# matrix_mixer_rev02_7eurorack.net
KiCad netlist of a schematic drawn in EAGLE
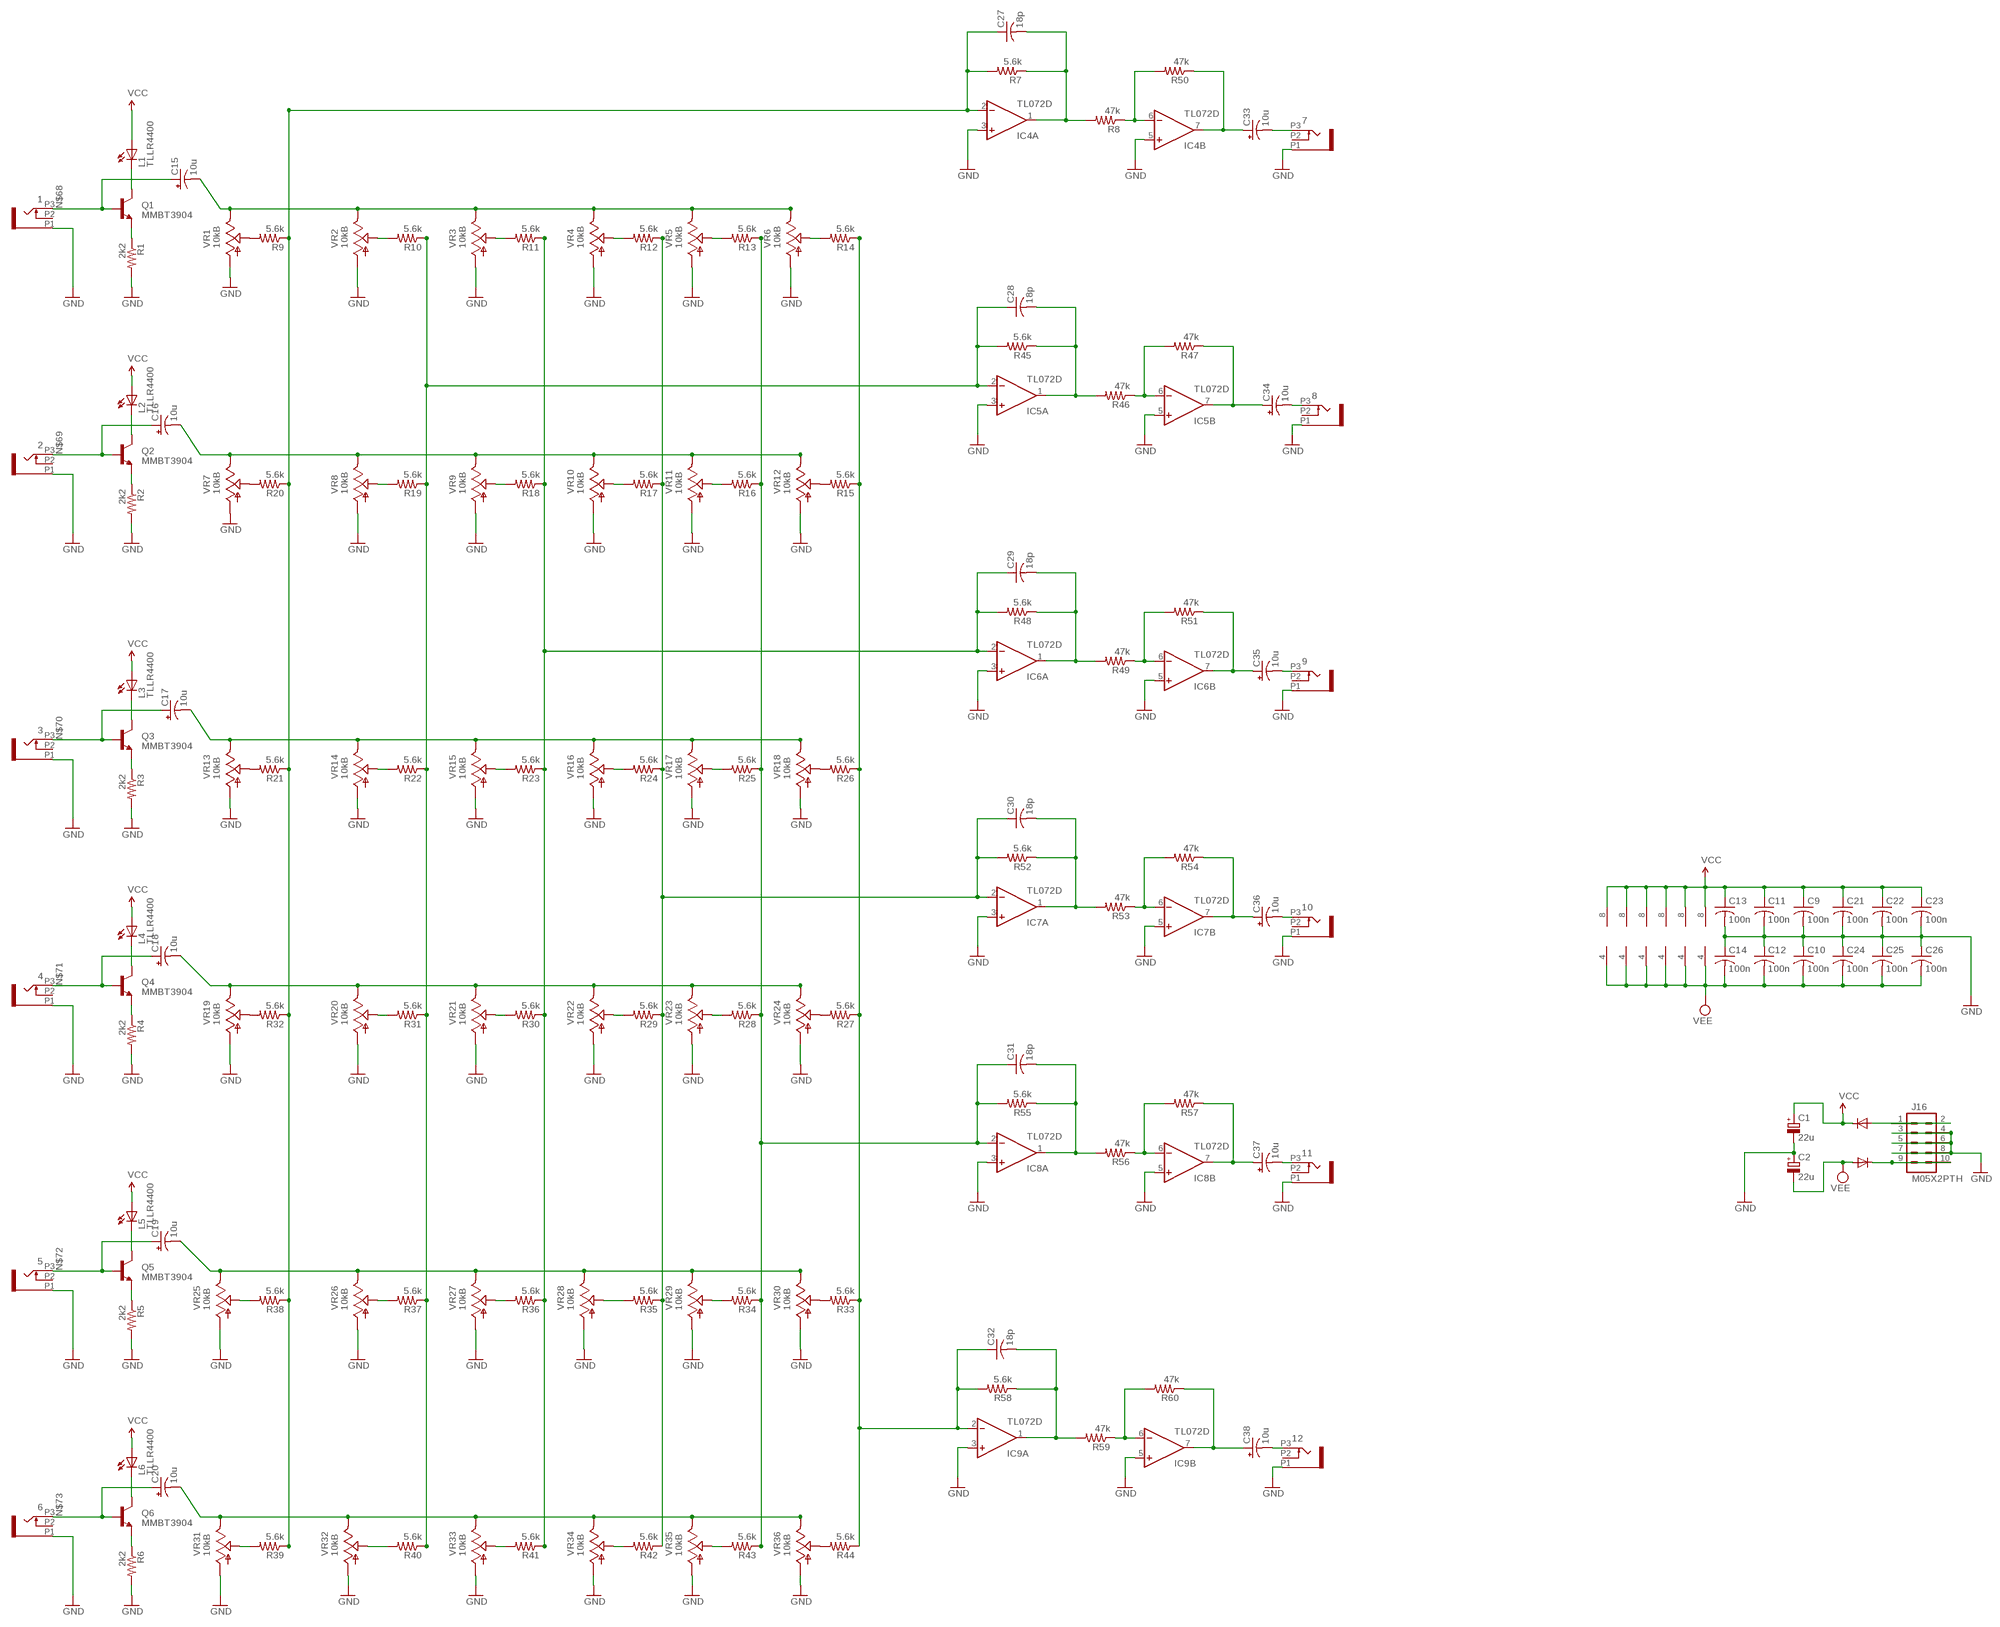
[diagram p0: schematic, sheet 1]

(export (version "E")
  (design (tool "Eeschema 10.0.6"))
  (components
    (comp (ref "1")
      (value "PJ301_THONKICONN6")
      (footprint "eagle-import:WQP_PJ_301M6")
      (libsource (lib "eagle-import") (part "PJ301_THONKICONN6"))
    )
    (comp (ref "2")
      (value "PJ301_THONKICONN6")
      (footprint "eagle-import:WQP_PJ_301M6")
      (libsource (lib "eagle-import") (part "PJ301_THONKICONN6"))
    )
    (comp (ref "3")
      (value "PJ301_THONKICONN6")
      (footprint "eagle-import:WQP_PJ_301M6")
      (libsource (lib "eagle-import") (part "PJ301_THONKICONN6"))
    )
    (comp (ref "4")
      (value "PJ301_THONKICONN6")
      (footprint "eagle-import:WQP_PJ_301M6")
      (libsource (lib "eagle-import") (part "PJ301_THONKICONN6"))
    )
    (comp (ref "5")
      (value "PJ301_THONKICONN6")
      (footprint "eagle-import:WQP_PJ_301M6")
      (libsource (lib "eagle-import") (part "PJ301_THONKICONN6"))
    )
    (comp (ref "6")
      (value "PJ301_THONKICONN6")
      (footprint "eagle-import:WQP_PJ_301M6")
      (libsource (lib "eagle-import") (part "PJ301_THONKICONN6"))
    )
    (comp (ref "7")
      (value "PJ301_THONKICONN6")
      (footprint "eagle-import:WQP_PJ_301M6")
      (libsource (lib "eagle-import") (part "PJ301_THONKICONN6"))
    )
    (comp (ref "8")
      (value "PJ301_THONKICONN6")
      (footprint "eagle-import:WQP_PJ_301M6")
      (libsource (lib "eagle-import") (part "PJ301_THONKICONN6"))
    )
    (comp (ref "9")
      (value "PJ301_THONKICONN6")
      (footprint "eagle-import:WQP_PJ_301M6")
      (libsource (lib "eagle-import") (part "PJ301_THONKICONN6"))
    )
    (comp (ref "10")
      (value "PJ301_THONKICONN6")
      (footprint "eagle-import:WQP_PJ_301M6")
      (libsource (lib "eagle-import") (part "PJ301_THONKICONN6"))
    )
    (comp (ref "11")
      (value "PJ301_THONKICONN6")
      (footprint "eagle-import:WQP_PJ_301M6")
      (libsource (lib "eagle-import") (part "PJ301_THONKICONN6"))
    )
    (comp (ref "12")
      (value "PJ301_THONKICONN6")
      (footprint "eagle-import:WQP_PJ_301M6")
      (libsource (lib "eagle-import") (part "PJ301_THONKICONN6"))
    )
    (comp (ref "C1")
      (value "22u")
      (footprint "eagle-import:PANASONIC_D")
      (libsource (lib "eagle-import") (part "CPOL-EUD"))
    )
    (comp (ref "C2")
      (value "22u")
      (footprint "eagle-import:PANASONIC_D")
      (libsource (lib "eagle-import") (part "CPOL-EUD"))
    )
    (comp (ref "C9")
      (value "100n")
      (footprint "eagle-import:C0603")
      (libsource (lib "eagle-import") (part "C-USC0603"))
    )
    (comp (ref "C10")
      (value "100n")
      (footprint "eagle-import:C0603")
      (libsource (lib "eagle-import") (part "C-USC0603"))
    )
    (comp (ref "C11")
      (value "100n")
      (footprint "eagle-import:C0603")
      (libsource (lib "eagle-import") (part "C-USC0603"))
    )
    (comp (ref "C12")
      (value "100n")
      (footprint "eagle-import:C0603")
      (libsource (lib "eagle-import") (part "C-USC0603"))
    )
    (comp (ref "C13")
      (value "100n")
      (footprint "eagle-import:C0603")
      (libsource (lib "eagle-import") (part "C-USC0603"))
    )
    (comp (ref "C14")
      (value "100n")
      (footprint "eagle-import:C0603")
      (libsource (lib "eagle-import") (part "C-USC0603"))
    )
    (comp (ref "C15")
      (value "10u")
      (footprint "eagle-import:PANASONIC_B")
      (libsource (lib "eagle-import") (part "CPOL-USB"))
    )
    (comp (ref "C16")
      (value "10u")
      (footprint "eagle-import:PANASONIC_B")
      (libsource (lib "eagle-import") (part "CPOL-USB"))
    )
    (comp (ref "C17")
      (value "10u")
      (footprint "eagle-import:PANASONIC_B")
      (libsource (lib "eagle-import") (part "CPOL-USB"))
    )
    (comp (ref "C18")
      (value "10u")
      (footprint "eagle-import:PANASONIC_B")
      (libsource (lib "eagle-import") (part "CPOL-USB"))
    )
    (comp (ref "C19")
      (value "10u")
      (footprint "eagle-import:PANASONIC_B")
      (libsource (lib "eagle-import") (part "CPOL-USB"))
    )
    (comp (ref "C20")
      (value "10u")
      (footprint "eagle-import:PANASONIC_B")
      (libsource (lib "eagle-import") (part "CPOL-USB"))
    )
    (comp (ref "C21")
      (value "100n")
      (footprint "eagle-import:C0603")
      (libsource (lib "eagle-import") (part "C-USC0603"))
    )
    (comp (ref "C22")
      (value "100n")
      (footprint "eagle-import:C0603")
      (libsource (lib "eagle-import") (part "C-USC0603"))
    )
    (comp (ref "C23")
      (value "100n")
      (footprint "eagle-import:C0603")
      (libsource (lib "eagle-import") (part "C-USC0603"))
    )
    (comp (ref "C24")
      (value "100n")
      (footprint "eagle-import:C0603")
      (libsource (lib "eagle-import") (part "C-USC0603"))
    )
    (comp (ref "C25")
      (value "100n")
      (footprint "eagle-import:C0603")
      (libsource (lib "eagle-import") (part "C-USC0603"))
    )
    (comp (ref "C26")
      (value "100n")
      (footprint "eagle-import:C0603")
      (libsource (lib "eagle-import") (part "C-USC0603"))
    )
    (comp (ref "C27")
      (value "18p")
      (footprint "eagle-import:C0603")
      (libsource (lib "eagle-import") (part "C-USC0603"))
    )
    (comp (ref "C28")
      (value "18p")
      (footprint "eagle-import:C0603")
      (libsource (lib "eagle-import") (part "C-USC0603"))
    )
    (comp (ref "C29")
      (value "18p")
      (footprint "eagle-import:C0603")
      (libsource (lib "eagle-import") (part "C-USC0603"))
    )
    (comp (ref "C30")
      (value "18p")
      (footprint "eagle-import:C0603")
      (libsource (lib "eagle-import") (part "C-USC0603"))
    )
    (comp (ref "C31")
      (value "18p")
      (footprint "eagle-import:C0603")
      (libsource (lib "eagle-import") (part "C-USC0603"))
    )
    (comp (ref "C32")
      (value "18p")
      (footprint "eagle-import:C0603")
      (libsource (lib "eagle-import") (part "C-USC0603"))
    )
    (comp (ref "C33")
      (value "10u")
      (footprint "eagle-import:PANASONIC_B")
      (libsource (lib "eagle-import") (part "CPOL-USB"))
    )
    (comp (ref "C34")
      (value "10u")
      (footprint "eagle-import:PANASONIC_B")
      (libsource (lib "eagle-import") (part "CPOL-USB"))
    )
    (comp (ref "C35")
      (value "10u")
      (footprint "eagle-import:PANASONIC_B")
      (libsource (lib "eagle-import") (part "CPOL-USB"))
    )
    (comp (ref "C36")
      (value "10u")
      (footprint "eagle-import:PANASONIC_B")
      (libsource (lib "eagle-import") (part "CPOL-USB"))
    )
    (comp (ref "C37")
      (value "10u")
      (footprint "eagle-import:PANASONIC_B")
      (libsource (lib "eagle-import") (part "CPOL-USB"))
    )
    (comp (ref "C38")
      (value "10u")
      (footprint "eagle-import:PANASONIC_B")
      (libsource (lib "eagle-import") (part "CPOL-USB"))
    )
    (comp (ref "D1")
      (value "1N5819HW")
      (footprint "eagle-import:SOD123")
      (libsource (lib "eagle-import") (part "DIODE-SOD123"))
    )
    (comp (ref "D2")
      (value "1N5819HW")
      (footprint "eagle-import:SOD123")
      (libsource (lib "eagle-import") (part "DIODE-SOD123"))
    )
    (comp (ref "IC4")
      (value "TL072D")
      (footprint "eagle-import:SO08")
      (libsource (lib "eagle-import") (part "TL072D"))
    )
    (comp (ref "IC5")
      (value "TL072D")
      (footprint "eagle-import:SO08")
      (libsource (lib "eagle-import") (part "TL072D"))
    )
    (comp (ref "IC6")
      (value "TL072D")
      (footprint "eagle-import:SO08")
      (libsource (lib "eagle-import") (part "TL072D"))
    )
    (comp (ref "IC7")
      (value "TL072D")
      (footprint "eagle-import:SO08")
      (libsource (lib "eagle-import") (part "TL072D"))
    )
    (comp (ref "IC8")
      (value "TL072D")
      (footprint "eagle-import:SO08")
      (libsource (lib "eagle-import") (part "TL072D"))
    )
    (comp (ref "IC9")
      (value "TL072D")
      (footprint "eagle-import:SO08")
      (libsource (lib "eagle-import") (part "TL072D"))
    )
    (comp (ref "J16")
      (value "M05X2PTH")
      (footprint "eagle-import:AVR_ICSP")
      (libsource (lib "eagle-import") (part "M05X2PTH"))
    )
    (comp (ref "L1")
      (value "TLLR4400")
      (footprint "eagle-import:LED3MM")
      (fields (field (name "MF") "VISHAY SEMICONDUCTOR"))
      (libsource (lib "eagle-import") (part "TLLR4400"))
    )
    (comp (ref "L2")
      (value "TLLR4400")
      (footprint "eagle-import:LED3MM")
      (fields (field (name "MF") "VISHAY SEMICONDUCTOR"))
      (libsource (lib "eagle-import") (part "TLLR4400"))
    )
    (comp (ref "L3")
      (value "TLLR4400")
      (footprint "eagle-import:LED3MM")
      (fields (field (name "MF") "VISHAY SEMICONDUCTOR"))
      (libsource (lib "eagle-import") (part "TLLR4400"))
    )
    (comp (ref "L4")
      (value "TLLR4400")
      (footprint "eagle-import:LED3MM")
      (fields (field (name "MF") "VISHAY SEMICONDUCTOR"))
      (libsource (lib "eagle-import") (part "TLLR4400"))
    )
    (comp (ref "L5")
      (value "TLLR4400")
      (footprint "eagle-import:LED3MM")
      (fields (field (name "MF") "VISHAY SEMICONDUCTOR"))
      (libsource (lib "eagle-import") (part "TLLR4400"))
    )
    (comp (ref "L6")
      (value "TLLR4400")
      (footprint "eagle-import:LED3MM")
      (fields (field (name "MF") "VISHAY SEMICONDUCTOR"))
      (libsource (lib "eagle-import") (part "TLLR4400"))
    )
    (comp (ref "Q1")
      (value "MMBT3904")
      (footprint "eagle-import:SOT23-BEC")
      (libsource (lib "eagle-import") (part "-NPN-SOT23-BECMMBT3904LT1"))
    )
    (comp (ref "Q2")
      (value "MMBT3904")
      (footprint "eagle-import:SOT23-BEC")
      (libsource (lib "eagle-import") (part "-NPN-SOT23-BECMMBT3904LT1"))
    )
    (comp (ref "Q3")
      (value "MMBT3904")
      (footprint "eagle-import:SOT23-BEC")
      (libsource (lib "eagle-import") (part "-NPN-SOT23-BECMMBT3904LT1"))
    )
    (comp (ref "Q4")
      (value "MMBT3904")
      (footprint "eagle-import:SOT23-BEC")
      (libsource (lib "eagle-import") (part "-NPN-SOT23-BECMMBT3904LT1"))
    )
    (comp (ref "Q5")
      (value "MMBT3904")
      (footprint "eagle-import:SOT23-BEC")
      (libsource (lib "eagle-import") (part "-NPN-SOT23-BECMMBT3904LT1"))
    )
    (comp (ref "Q6")
      (value "MMBT3904")
      (footprint "eagle-import:SOT23-BEC")
      (libsource (lib "eagle-import") (part "-NPN-SOT23-BECMMBT3904LT1"))
    )
    (comp (ref "R1")
      (value "2k2")
      (footprint "eagle-import:R0603")
      (libsource (lib "eagle-import") (part "R-US_R0603"))
    )
    (comp (ref "R2")
      (value "2k2")
      (footprint "eagle-import:R0603")
      (libsource (lib "eagle-import") (part "R-US_R0603"))
    )
    (comp (ref "R3")
      (value "2k2")
      (footprint "eagle-import:R0603")
      (libsource (lib "eagle-import") (part "R-US_R0603"))
    )
    (comp (ref "R4")
      (value "2k2")
      (footprint "eagle-import:R0603")
      (libsource (lib "eagle-import") (part "R-US_R0603"))
    )
    (comp (ref "R5")
      (value "2k2")
      (footprint "eagle-import:R0603")
      (libsource (lib "eagle-import") (part "R-US_R0603"))
    )
    (comp (ref "R6")
      (value "2k2")
      (footprint "eagle-import:R0603")
      (libsource (lib "eagle-import") (part "R-US_R0603"))
    )
    (comp (ref "R7")
      (value "5.6k")
      (footprint "eagle-import:R0603")
      (libsource (lib "eagle-import") (part "R-US_R0603"))
    )
    (comp (ref "R8")
      (value "47k")
      (footprint "eagle-import:R0603")
      (libsource (lib "eagle-import") (part "R-US_R0603"))
    )
    (comp (ref "R9")
      (value "5.6k")
      (footprint "eagle-import:R0603")
      (libsource (lib "eagle-import") (part "R-US_R0603"))
    )
    (comp (ref "R10")
      (value "5.6k")
      (footprint "eagle-import:R0603")
      (libsource (lib "eagle-import") (part "R-US_R0603"))
    )
    (comp (ref "R11")
      (value "5.6k")
      (footprint "eagle-import:R0603")
      (libsource (lib "eagle-import") (part "R-US_R0603"))
    )
    (comp (ref "R12")
      (value "5.6k")
      (footprint "eagle-import:R0603")
      (libsource (lib "eagle-import") (part "R-US_R0603"))
    )
    (comp (ref "R13")
      (value "5.6k")
      (footprint "eagle-import:R0603")
      (libsource (lib "eagle-import") (part "R-US_R0603"))
    )
    (comp (ref "R14")
      (value "5.6k")
      (footprint "eagle-import:R0603")
      (libsource (lib "eagle-import") (part "R-US_R0603"))
    )
    (comp (ref "R15")
      (value "5.6k")
      (footprint "eagle-import:R0603")
      (libsource (lib "eagle-import") (part "R-US_R0603"))
    )
    (comp (ref "R16")
      (value "5.6k")
      (footprint "eagle-import:R0603")
      (libsource (lib "eagle-import") (part "R-US_R0603"))
    )
    (comp (ref "R17")
      (value "5.6k")
      (footprint "eagle-import:R0603")
      (libsource (lib "eagle-import") (part "R-US_R0603"))
    )
    (comp (ref "R18")
      (value "5.6k")
      (footprint "eagle-import:R0603")
      (libsource (lib "eagle-import") (part "R-US_R0603"))
    )
    (comp (ref "R19")
      (value "5.6k")
      (footprint "eagle-import:R0603")
      (libsource (lib "eagle-import") (part "R-US_R0603"))
    )
    (comp (ref "R20")
      (value "5.6k")
      (footprint "eagle-import:R0603")
      (libsource (lib "eagle-import") (part "R-US_R0603"))
    )
    (comp (ref "R21")
      (value "5.6k")
      (footprint "eagle-import:R0603")
      (libsource (lib "eagle-import") (part "R-US_R0603"))
    )
    (comp (ref "R22")
      (value "5.6k")
      (footprint "eagle-import:R0603")
      (libsource (lib "eagle-import") (part "R-US_R0603"))
    )
    (comp (ref "R23")
      (value "5.6k")
      (footprint "eagle-import:R0603")
      (libsource (lib "eagle-import") (part "R-US_R0603"))
    )
    (comp (ref "R24")
      (value "5.6k")
      (footprint "eagle-import:R0603")
      (libsource (lib "eagle-import") (part "R-US_R0603"))
    )
    (comp (ref "R25")
      (value "5.6k")
      (footprint "eagle-import:R0603")
      (libsource (lib "eagle-import") (part "R-US_R0603"))
    )
    (comp (ref "R26")
      (value "5.6k")
      (footprint "eagle-import:R0603")
      (libsource (lib "eagle-import") (part "R-US_R0603"))
    )
    (comp (ref "R27")
      (value "5.6k")
      (footprint "eagle-import:R0603")
      (libsource (lib "eagle-import") (part "R-US_R0603"))
    )
    (comp (ref "R28")
      (value "5.6k")
      (footprint "eagle-import:R0603")
      (libsource (lib "eagle-import") (part "R-US_R0603"))
    )
    (comp (ref "R29")
      (value "5.6k")
      (footprint "eagle-import:R0603")
      (libsource (lib "eagle-import") (part "R-US_R0603"))
    )
    (comp (ref "R30")
      (value "5.6k")
      (footprint "eagle-import:R0603")
      (libsource (lib "eagle-import") (part "R-US_R0603"))
    )
    (comp (ref "R31")
      (value "5.6k")
      (footprint "eagle-import:R0603")
      (libsource (lib "eagle-import") (part "R-US_R0603"))
    )
    (comp (ref "R32")
      (value "5.6k")
      (footprint "eagle-import:R0603")
      (libsource (lib "eagle-import") (part "R-US_R0603"))
    )
    (comp (ref "R33")
      (value "5.6k")
      (footprint "eagle-import:R0603")
      (libsource (lib "eagle-import") (part "R-US_R0603"))
    )
    (comp (ref "R34")
      (value "5.6k")
      (footprint "eagle-import:R0603")
      (libsource (lib "eagle-import") (part "R-US_R0603"))
    )
    (comp (ref "R35")
      (value "5.6k")
      (footprint "eagle-import:R0603")
      (libsource (lib "eagle-import") (part "R-US_R0603"))
    )
    (comp (ref "R36")
      (value "5.6k")
      (footprint "eagle-import:R0603")
      (libsource (lib "eagle-import") (part "R-US_R0603"))
    )
    (comp (ref "R37")
      (value "5.6k")
      (footprint "eagle-import:R0603")
      (libsource (lib "eagle-import") (part "R-US_R0603"))
    )
    (comp (ref "R38")
      (value "5.6k")
      (footprint "eagle-import:R0603")
      (libsource (lib "eagle-import") (part "R-US_R0603"))
    )
    (comp (ref "R39")
      (value "5.6k")
      (footprint "eagle-import:R0603")
      (libsource (lib "eagle-import") (part "R-US_R0603"))
    )
    (comp (ref "R40")
      (value "5.6k")
      (footprint "eagle-import:R0603")
      (libsource (lib "eagle-import") (part "R-US_R0603"))
    )
    (comp (ref "R41")
      (value "5.6k")
      (footprint "eagle-import:R0603")
      (libsource (lib "eagle-import") (part "R-US_R0603"))
    )
    (comp (ref "R42")
      (value "5.6k")
      (footprint "eagle-import:R0603")
      (libsource (lib "eagle-import") (part "R-US_R0603"))
    )
    (comp (ref "R43")
      (value "5.6k")
      (footprint "eagle-import:R0603")
      (libsource (lib "eagle-import") (part "R-US_R0603"))
    )
    (comp (ref "R44")
      (value "5.6k")
      (footprint "eagle-import:R0603")
      (libsource (lib "eagle-import") (part "R-US_R0603"))
    )
    (comp (ref "R45")
      (value "5.6k")
      (footprint "eagle-import:R0603")
      (libsource (lib "eagle-import") (part "R-US_R0603"))
    )
    (comp (ref "R46")
      (value "47k")
      (footprint "eagle-import:R0603")
      (libsource (lib "eagle-import") (part "R-US_R0603"))
    )
    (comp (ref "R47")
      (value "47k")
      (footprint "eagle-import:R0603")
      (libsource (lib "eagle-import") (part "R-US_R0603"))
    )
    (comp (ref "R48")
      (value "5.6k")
      (footprint "eagle-import:R0603")
      (libsource (lib "eagle-import") (part "R-US_R0603"))
    )
    (comp (ref "R49")
      (value "47k")
      (footprint "eagle-import:R0603")
      (libsource (lib "eagle-import") (part "R-US_R0603"))
    )
    (comp (ref "R50")
      (value "47k")
      (footprint "eagle-import:R0603")
      (libsource (lib "eagle-import") (part "R-US_R0603"))
    )
    (comp (ref "R51")
      (value "47k")
      (footprint "eagle-import:R0603")
      (libsource (lib "eagle-import") (part "R-US_R0603"))
    )
    (comp (ref "R52")
      (value "5.6k")
      (footprint "eagle-import:R0603")
      (libsource (lib "eagle-import") (part "R-US_R0603"))
    )
    (comp (ref "R53")
      (value "47k")
      (footprint "eagle-import:R0603")
      (libsource (lib "eagle-import") (part "R-US_R0603"))
    )
    (comp (ref "R54")
      (value "47k")
      (footprint "eagle-import:R0603")
      (libsource (lib "eagle-import") (part "R-US_R0603"))
    )
    (comp (ref "R55")
      (value "5.6k")
      (footprint "eagle-import:R0603")
      (libsource (lib "eagle-import") (part "R-US_R0603"))
    )
    (comp (ref "R56")
      (value "47k")
      (footprint "eagle-import:R0603")
      (libsource (lib "eagle-import") (part "R-US_R0603"))
    )
    (comp (ref "R57")
      (value "47k")
      (footprint "eagle-import:R0603")
      (libsource (lib "eagle-import") (part "R-US_R0603"))
    )
    (comp (ref "R58")
      (value "5.6k")
      (footprint "eagle-import:R0603")
      (libsource (lib "eagle-import") (part "R-US_R0603"))
    )
    (comp (ref "R59")
      (value "47k")
      (footprint "eagle-import:R0603")
      (libsource (lib "eagle-import") (part "R-US_R0603"))
    )
    (comp (ref "R60")
      (value "47k")
      (footprint "eagle-import:R0603")
      (libsource (lib "eagle-import") (part "R-US_R0603"))
    )
    (comp (ref "VR1")
      (value "10kB")
      (footprint "eagle-import:ALPS_POT_VERTICAL_PS")
      (libsource (lib "eagle-import") (part "POT_USVERTICAL_PS"))
    )
    (comp (ref "VR2")
      (value "10kB")
      (footprint "eagle-import:ALPS_POT_VERTICAL_PS")
      (libsource (lib "eagle-import") (part "POT_USVERTICAL_PS"))
    )
    (comp (ref "VR3")
      (value "10kB")
      (footprint "eagle-import:ALPS_POT_VERTICAL_PS")
      (libsource (lib "eagle-import") (part "POT_USVERTICAL_PS"))
    )
    (comp (ref "VR4")
      (value "10kB")
      (footprint "eagle-import:ALPS_POT_VERTICAL_PS")
      (libsource (lib "eagle-import") (part "POT_USVERTICAL_PS"))
    )
    (comp (ref "VR5")
      (value "10kB")
      (footprint "eagle-import:ALPS_POT_VERTICAL_PS")
      (libsource (lib "eagle-import") (part "POT_USVERTICAL_PS"))
    )
    (comp (ref "VR6")
      (value "10kB")
      (footprint "eagle-import:ALPS_POT_VERTICAL_PS")
      (libsource (lib "eagle-import") (part "POT_USVERTICAL_PS"))
    )
    (comp (ref "VR7")
      (value "10kB")
      (footprint "eagle-import:ALPS_POT_VERTICAL_PS")
      (libsource (lib "eagle-import") (part "POT_USVERTICAL_PS"))
    )
    (comp (ref "VR8")
      (value "10kB")
      (footprint "eagle-import:ALPS_POT_VERTICAL_PS")
      (libsource (lib "eagle-import") (part "POT_USVERTICAL_PS"))
    )
    (comp (ref "VR9")
      (value "10kB")
      (footprint "eagle-import:ALPS_POT_VERTICAL_PS")
      (libsource (lib "eagle-import") (part "POT_USVERTICAL_PS"))
    )
    (comp (ref "VR10")
      (value "10kB")
      (footprint "eagle-import:ALPS_POT_VERTICAL_PS")
      (libsource (lib "eagle-import") (part "POT_USVERTICAL_PS"))
    )
    (comp (ref "VR11")
      (value "10kB")
      (footprint "eagle-import:ALPS_POT_VERTICAL_PS")
      (libsource (lib "eagle-import") (part "POT_USVERTICAL_PS"))
    )
    (comp (ref "VR12")
      (value "10kB")
      (footprint "eagle-import:ALPS_POT_VERTICAL_PS")
      (libsource (lib "eagle-import") (part "POT_USVERTICAL_PS"))
    )
    (comp (ref "VR13")
      (value "10kB")
      (footprint "eagle-import:ALPS_POT_VERTICAL_PS")
      (libsource (lib "eagle-import") (part "POT_USVERTICAL_PS"))
    )
    (comp (ref "VR14")
      (value "10kB")
      (footprint "eagle-import:ALPS_POT_VERTICAL_PS")
      (libsource (lib "eagle-import") (part "POT_USVERTICAL_PS"))
    )
    (comp (ref "VR15")
      (value "10kB")
      (footprint "eagle-import:ALPS_POT_VERTICAL_PS")
      (libsource (lib "eagle-import") (part "POT_USVERTICAL_PS"))
    )
    (comp (ref "VR16")
      (value "10kB")
      (footprint "eagle-import:ALPS_POT_VERTICAL_PS")
      (libsource (lib "eagle-import") (part "POT_USVERTICAL_PS"))
    )
    (comp (ref "VR17")
      (value "10kB")
      (footprint "eagle-import:ALPS_POT_VERTICAL_PS")
      (libsource (lib "eagle-import") (part "POT_USVERTICAL_PS"))
    )
    (comp (ref "VR18")
      (value "10kB")
      (footprint "eagle-import:ALPS_POT_VERTICAL_PS")
      (libsource (lib "eagle-import") (part "POT_USVERTICAL_PS"))
    )
    (comp (ref "VR19")
      (value "10kB")
      (footprint "eagle-import:ALPS_POT_VERTICAL_PS")
      (libsource (lib "eagle-import") (part "POT_USVERTICAL_PS"))
    )
    (comp (ref "VR20")
      (value "10kB")
      (footprint "eagle-import:ALPS_POT_VERTICAL_PS")
      (libsource (lib "eagle-import") (part "POT_USVERTICAL_PS"))
    )
    (comp (ref "VR21")
      (value "10kB")
      (footprint "eagle-import:ALPS_POT_VERTICAL_PS")
      (libsource (lib "eagle-import") (part "POT_USVERTICAL_PS"))
    )
    (comp (ref "VR22")
      (value "10kB")
      (footprint "eagle-import:ALPS_POT_VERTICAL_PS")
      (libsource (lib "eagle-import") (part "POT_USVERTICAL_PS"))
    )
    (comp (ref "VR23")
      (value "10kB")
      (footprint "eagle-import:ALPS_POT_VERTICAL_PS")
      (libsource (lib "eagle-import") (part "POT_USVERTICAL_PS"))
    )
    (comp (ref "VR24")
      (value "10kB")
      (footprint "eagle-import:ALPS_POT_VERTICAL_PS")
      (libsource (lib "eagle-import") (part "POT_USVERTICAL_PS"))
    )
    (comp (ref "VR25")
      (value "10kB")
      (footprint "eagle-import:ALPS_POT_VERTICAL_PS")
      (libsource (lib "eagle-import") (part "POT_USVERTICAL_PS"))
    )
    (comp (ref "VR26")
      (value "10kB")
      (footprint "eagle-import:ALPS_POT_VERTICAL_PS")
      (libsource (lib "eagle-import") (part "POT_USVERTICAL_PS"))
    )
    (comp (ref "VR27")
      (value "10kB")
      (footprint "eagle-import:ALPS_POT_VERTICAL_PS")
      (libsource (lib "eagle-import") (part "POT_USVERTICAL_PS"))
    )
    (comp (ref "VR28")
      (value "10kB")
      (footprint "eagle-import:ALPS_POT_VERTICAL_PS")
      (libsource (lib "eagle-import") (part "POT_USVERTICAL_PS"))
    )
    (comp (ref "VR29")
      (value "10kB")
      (footprint "eagle-import:ALPS_POT_VERTICAL_PS")
      (libsource (lib "eagle-import") (part "POT_USVERTICAL_PS"))
    )
    (comp (ref "VR30")
      (value "10kB")
      (footprint "eagle-import:ALPS_POT_VERTICAL_PS")
      (libsource (lib "eagle-import") (part "POT_USVERTICAL_PS"))
    )
    (comp (ref "VR31")
      (value "10kB")
      (footprint "eagle-import:ALPS_POT_VERTICAL_PS")
      (libsource (lib "eagle-import") (part "POT_USVERTICAL_PS"))
    )
    (comp (ref "VR32")
      (value "10kB")
      (footprint "eagle-import:ALPS_POT_VERTICAL_PS")
      (libsource (lib "eagle-import") (part "POT_USVERTICAL_PS"))
    )
    (comp (ref "VR33")
      (value "10kB")
      (footprint "eagle-import:ALPS_POT_VERTICAL_PS")
      (libsource (lib "eagle-import") (part "POT_USVERTICAL_PS"))
    )
    (comp (ref "VR34")
      (value "10kB")
      (footprint "eagle-import:ALPS_POT_VERTICAL_PS")
      (libsource (lib "eagle-import") (part "POT_USVERTICAL_PS"))
    )
    (comp (ref "VR35")
      (value "10kB")
      (footprint "eagle-import:ALPS_POT_VERTICAL_PS")
      (libsource (lib "eagle-import") (part "POT_USVERTICAL_PS"))
    )
    (comp (ref "VR36")
      (value "10kB")
      (footprint "eagle-import:ALPS_POT_VERTICAL_PS")
      (libsource (lib "eagle-import") (part "POT_USVERTICAL_PS"))
    )
  )
  (nets
    (net (code "1") (name "/N$68") (class "Default")
      (node (ref "1") (pin "P3") (pinfunction "3_P3") (pintype "passive"))
      (node (ref "C15") (pin "+") (pinfunction "+_+") (pintype "passive"))
      (node (ref "Q1") (pin "B") (pinfunction "B_B") (pintype "passive"))
    )
    (net (code "2") (name "/N$69") (class "Default")
      (node (ref "2") (pin "P3") (pinfunction "3_P3") (pintype "passive"))
      (node (ref "C16") (pin "+") (pinfunction "+_+") (pintype "passive"))
      (node (ref "Q2") (pin "B") (pinfunction "B_B") (pintype "passive"))
    )
    (net (code "3") (name "/N$70") (class "Default")
      (node (ref "3") (pin "P3") (pinfunction "3_P3") (pintype "passive"))
      (node (ref "C17") (pin "+") (pinfunction "+_+") (pintype "passive"))
      (node (ref "Q3") (pin "B") (pinfunction "B_B") (pintype "passive"))
    )
    (net (code "4") (name "/N$71") (class "Default")
      (node (ref "4") (pin "P3") (pinfunction "3_P3") (pintype "passive"))
      (node (ref "C18") (pin "+") (pinfunction "+_+") (pintype "passive"))
      (node (ref "Q4") (pin "B") (pinfunction "B_B") (pintype "passive"))
    )
    (net (code "5") (name "/N$72") (class "Default")
      (node (ref "5") (pin "P3") (pinfunction "3_P3") (pintype "passive"))
      (node (ref "C19") (pin "+") (pinfunction "+_+") (pintype "passive"))
      (node (ref "Q5") (pin "B") (pinfunction "B_B") (pintype "passive"))
    )
    (net (code "6") (name "/N$73") (class "Default")
      (node (ref "6") (pin "P3") (pinfunction "3_P3") (pintype "passive"))
      (node (ref "C20") (pin "+") (pinfunction "+_+") (pintype "passive"))
      (node (ref "Q6") (pin "B") (pinfunction "B_B") (pintype "passive"))
    )
    (net (code "7") (name "GND") (class "Default")
      (node (ref "1") (pin "P1") (pinfunction "1_P1") (pintype "passive"))
      (node (ref "10") (pin "P1") (pinfunction "1_P1") (pintype "passive"))
      (node (ref "11") (pin "P1") (pinfunction "1_P1") (pintype "passive"))
      (node (ref "12") (pin "P1") (pinfunction "1_P1") (pintype "passive"))
      (node (ref "2") (pin "P1") (pinfunction "1_P1") (pintype "passive"))
      (node (ref "3") (pin "P1") (pinfunction "1_P1") (pintype "passive"))
      (node (ref "4") (pin "P1") (pinfunction "1_P1") (pintype "passive"))
      (node (ref "5") (pin "P1") (pinfunction "1_P1") (pintype "passive"))
      (node (ref "6") (pin "P1") (pinfunction "1_P1") (pintype "passive"))
      (node (ref "7") (pin "P1") (pinfunction "1_P1") (pintype "passive"))
      (node (ref "8") (pin "P1") (pinfunction "1_P1") (pintype "passive"))
      (node (ref "9") (pin "P1") (pinfunction "1_P1") (pintype "passive"))
      (node (ref "C1") (pin "-") (pinfunction "-_-") (pintype "passive"))
      (node (ref "C10") (pin "1") (pinfunction "1_1") (pintype "passive"))
      (node (ref "C11") (pin "2") (pinfunction "2_2") (pintype "passive"))
      (node (ref "C12") (pin "1") (pinfunction "1_1") (pintype "passive"))
      (node (ref "C13") (pin "2") (pinfunction "2_2") (pintype "passive"))
      (node (ref "C14") (pin "1") (pinfunction "1_1") (pintype "passive"))
      (node (ref "C2") (pin "+") (pinfunction "+_+") (pintype "passive"))
      (node (ref "C21") (pin "2") (pinfunction "2_2") (pintype "passive"))
      (node (ref "C22") (pin "2") (pinfunction "2_2") (pintype "passive"))
      (node (ref "C23") (pin "2") (pinfunction "2_2") (pintype "passive"))
      (node (ref "C24") (pin "1") (pinfunction "1_1") (pintype "passive"))
      (node (ref "C25") (pin "1") (pinfunction "1_1") (pintype "passive"))
      (node (ref "C26") (pin "1") (pinfunction "1_1") (pintype "passive"))
      (node (ref "C9") (pin "2") (pinfunction "2_2") (pintype "passive"))
      (node (ref "IC4") (pin "3") (pinfunction "+IN_3") (pintype "input"))
      (node (ref "IC4") (pin "5") (pinfunction "+IN_5") (pintype "input"))
      (node (ref "IC5") (pin "3") (pinfunction "+IN_3") (pintype "input"))
      (node (ref "IC5") (pin "5") (pinfunction "+IN_5") (pintype "input"))
      (node (ref "IC6") (pin "3") (pinfunction "+IN_3") (pintype "input"))
      (node (ref "IC6") (pin "5") (pinfunction "+IN_5") (pintype "input"))
      (node (ref "IC7") (pin "3") (pinfunction "+IN_3") (pintype "input"))
      (node (ref "IC7") (pin "5") (pinfunction "+IN_5") (pintype "input"))
      (node (ref "IC8") (pin "3") (pinfunction "+IN_3") (pintype "input"))
      (node (ref "IC8") (pin "5") (pinfunction "+IN_5") (pintype "input"))
      (node (ref "IC9") (pin "3") (pinfunction "+IN_3") (pintype "input"))
      (node (ref "IC9") (pin "5") (pinfunction "+IN_5") (pintype "input"))
      (node (ref "J16") (pin "3") (pinfunction "3_3") (pintype "passive"))
      (node (ref "J16") (pin "4") (pinfunction "4_4") (pintype "passive"))
      (node (ref "J16") (pin "5") (pinfunction "5_5") (pintype "passive"))
      (node (ref "J16") (pin "6") (pinfunction "6_6") (pintype "passive"))
      (node (ref "J16") (pin "7") (pinfunction "7_7") (pintype "passive"))
      (node (ref "J16") (pin "8") (pinfunction "8_8") (pintype "passive"))
      (node (ref "R1") (pin "2") (pinfunction "2_2") (pintype "passive"))
      (node (ref "R2") (pin "2") (pinfunction "2_2") (pintype "passive"))
      (node (ref "R3") (pin "2") (pinfunction "2_2") (pintype "passive"))
      (node (ref "R4") (pin "2") (pinfunction "2_2") (pintype "passive"))
      (node (ref "R5") (pin "2") (pinfunction "2_2") (pintype "passive"))
      (node (ref "R6") (pin "2") (pinfunction "2_2") (pintype "passive"))
      (node (ref "VR1") (pin "P$3") (pinfunction "A_P$3") (pintype "passive"))
      (node (ref "VR10") (pin "P$3") (pinfunction "A_P$3") (pintype "passive"))
      (node (ref "VR11") (pin "P$3") (pinfunction "A_P$3") (pintype "passive"))
      (node (ref "VR12") (pin "P$3") (pinfunction "A_P$3") (pintype "passive"))
      (node (ref "VR13") (pin "P$3") (pinfunction "A_P$3") (pintype "passive"))
      (node (ref "VR14") (pin "P$3") (pinfunction "A_P$3") (pintype "passive"))
      (node (ref "VR15") (pin "P$3") (pinfunction "A_P$3") (pintype "passive"))
      (node (ref "VR16") (pin "P$3") (pinfunction "A_P$3") (pintype "passive"))
      (node (ref "VR17") (pin "P$3") (pinfunction "A_P$3") (pintype "passive"))
      (node (ref "VR18") (pin "P$3") (pinfunction "A_P$3") (pintype "passive"))
      (node (ref "VR19") (pin "P$3") (pinfunction "A_P$3") (pintype "passive"))
      (node (ref "VR2") (pin "P$3") (pinfunction "A_P$3") (pintype "passive"))
      (node (ref "VR20") (pin "P$3") (pinfunction "A_P$3") (pintype "passive"))
      (node (ref "VR21") (pin "P$3") (pinfunction "A_P$3") (pintype "passive"))
      (node (ref "VR22") (pin "P$3") (pinfunction "A_P$3") (pintype "passive"))
      (node (ref "VR23") (pin "P$3") (pinfunction "A_P$3") (pintype "passive"))
      (node (ref "VR24") (pin "P$3") (pinfunction "A_P$3") (pintype "passive"))
      (node (ref "VR25") (pin "P$3") (pinfunction "A_P$3") (pintype "passive"))
      (node (ref "VR26") (pin "P$3") (pinfunction "A_P$3") (pintype "passive"))
      (node (ref "VR27") (pin "P$3") (pinfunction "A_P$3") (pintype "passive"))
      (node (ref "VR28") (pin "P$3") (pinfunction "A_P$3") (pintype "passive"))
      (node (ref "VR29") (pin "P$3") (pinfunction "A_P$3") (pintype "passive"))
      (node (ref "VR3") (pin "P$3") (pinfunction "A_P$3") (pintype "passive"))
      (node (ref "VR30") (pin "P$3") (pinfunction "A_P$3") (pintype "passive"))
      (node (ref "VR31") (pin "P$3") (pinfunction "A_P$3") (pintype "passive"))
      (node (ref "VR32") (pin "P$3") (pinfunction "A_P$3") (pintype "passive"))
      (node (ref "VR33") (pin "P$3") (pinfunction "A_P$3") (pintype "passive"))
      (node (ref "VR34") (pin "P$3") (pinfunction "A_P$3") (pintype "passive"))
      (node (ref "VR35") (pin "P$3") (pinfunction "A_P$3") (pintype "passive"))
      (node (ref "VR36") (pin "P$3") (pinfunction "A_P$3") (pintype "passive"))
      (node (ref "VR4") (pin "P$3") (pinfunction "A_P$3") (pintype "passive"))
      (node (ref "VR5") (pin "P$3") (pinfunction "A_P$3") (pintype "passive"))
      (node (ref "VR6") (pin "P$3") (pinfunction "A_P$3") (pintype "passive"))
      (node (ref "VR7") (pin "P$3") (pinfunction "A_P$3") (pintype "passive"))
      (node (ref "VR8") (pin "P$3") (pinfunction "A_P$3") (pintype "passive"))
      (node (ref "VR9") (pin "P$3") (pinfunction "A_P$3") (pintype "passive"))
    )
    (net (code "8") (name "Net-(7-3)") (class "Default")
      (node (ref "7") (pin "P3") (pinfunction "3_P3") (pintype "passive"))
      (node (ref "C33") (pin "-") (pinfunction "-_-") (pintype "passive"))
    )
    (net (code "9") (name "Net-(8-3)") (class "Default")
      (node (ref "8") (pin "P3") (pinfunction "3_P3") (pintype "passive"))
      (node (ref "C34") (pin "-") (pinfunction "-_-") (pintype "passive"))
    )
    (net (code "10") (name "Net-(9-3)") (class "Default")
      (node (ref "9") (pin "P3") (pinfunction "3_P3") (pintype "passive"))
      (node (ref "C35") (pin "-") (pinfunction "-_-") (pintype "passive"))
    )
    (net (code "11") (name "Net-(10-3)") (class "Default")
      (node (ref "10") (pin "P3") (pinfunction "3_P3") (pintype "passive"))
      (node (ref "C36") (pin "-") (pinfunction "-_-") (pintype "passive"))
    )
    (net (code "12") (name "Net-(11-3)") (class "Default")
      (node (ref "11") (pin "P3") (pinfunction "3_P3") (pintype "passive"))
      (node (ref "C37") (pin "-") (pinfunction "-_-") (pintype "passive"))
    )
    (net (code "13") (name "Net-(12-3)") (class "Default")
      (node (ref "12") (pin "P3") (pinfunction "3_P3") (pintype "passive"))
      (node (ref "C38") (pin "-") (pinfunction "-_-") (pintype "passive"))
    )
    (net (code "14") (name "Net-(D1-PadA)") (class "Default")
      (node (ref "D1") (pin "A") (pinfunction "A_A") (pintype "passive"))
      (node (ref "J16") (pin "1") (pinfunction "1_1") (pintype "passive"))
      (node (ref "J16") (pin "2") (pinfunction "2_2") (pintype "passive"))
    )
    (net (code "15") (name "Net-(D2-PadC)") (class "Default")
      (node (ref "D2") (pin "C") (pinfunction "C_C") (pintype "passive"))
      (node (ref "J16") (pin "10") (pinfunction "10_10") (pintype "passive"))
      (node (ref "J16") (pin "9") (pinfunction "9_9") (pintype "passive"))
    )
    (net (code "16") (name "Net-(IC4A--IN)") (class "Default")
      (node (ref "C27") (pin "1") (pinfunction "1_1") (pintype "passive"))
      (node (ref "IC4") (pin "2") (pinfunction "-IN_2") (pintype "input"))
      (node (ref "R20") (pin "1") (pinfunction "1_1") (pintype "passive"))
      (node (ref "R21") (pin "1") (pinfunction "1_1") (pintype "passive"))
      (node (ref "R32") (pin "1") (pinfunction "1_1") (pintype "passive"))
      (node (ref "R38") (pin "1") (pinfunction "1_1") (pintype "passive"))
      (node (ref "R39") (pin "1") (pinfunction "1_1") (pintype "passive"))
      (node (ref "R7") (pin "2") (pinfunction "2_2") (pintype "passive"))
      (node (ref "R9") (pin "1") (pinfunction "1_1") (pintype "passive"))
    )
    (net (code "17") (name "Net-(IC4A-OUT)") (class "Default")
      (node (ref "C27") (pin "2") (pinfunction "2_2") (pintype "passive"))
      (node (ref "IC4") (pin "1") (pinfunction "OUT_1") (pintype "output"))
      (node (ref "R7") (pin "1") (pinfunction "1_1") (pintype "passive"))
      (node (ref "R8") (pin "2") (pinfunction "2_2") (pintype "passive"))
    )
    (net (code "18") (name "Net-(IC4B--IN)") (class "Default")
      (node (ref "IC4") (pin "6") (pinfunction "-IN_6") (pintype "input"))
      (node (ref "R50") (pin "2") (pinfunction "2_2") (pintype "passive"))
      (node (ref "R8") (pin "1") (pinfunction "1_1") (pintype "passive"))
    )
    (net (code "19") (name "Net-(IC4B-OUT)") (class "Default")
      (node (ref "C33") (pin "+") (pinfunction "+_+") (pintype "passive"))
      (node (ref "IC4") (pin "7") (pinfunction "OUT_7") (pintype "output"))
      (node (ref "R50") (pin "1") (pinfunction "1_1") (pintype "passive"))
    )
    (net (code "20") (name "Net-(IC5A--IN)") (class "Default")
      (node (ref "C28") (pin "1") (pinfunction "1_1") (pintype "passive"))
      (node (ref "IC5") (pin "2") (pinfunction "-IN_2") (pintype "input"))
      (node (ref "R10") (pin "1") (pinfunction "1_1") (pintype "passive"))
      (node (ref "R19") (pin "1") (pinfunction "1_1") (pintype "passive"))
      (node (ref "R22") (pin "1") (pinfunction "1_1") (pintype "passive"))
      (node (ref "R31") (pin "1") (pinfunction "1_1") (pintype "passive"))
      (node (ref "R37") (pin "1") (pinfunction "1_1") (pintype "passive"))
      (node (ref "R40") (pin "1") (pinfunction "1_1") (pintype "passive"))
      (node (ref "R45") (pin "2") (pinfunction "2_2") (pintype "passive"))
    )
    (net (code "21") (name "Net-(IC5A-OUT)") (class "Default")
      (node (ref "C28") (pin "2") (pinfunction "2_2") (pintype "passive"))
      (node (ref "IC5") (pin "1") (pinfunction "OUT_1") (pintype "output"))
      (node (ref "R45") (pin "1") (pinfunction "1_1") (pintype "passive"))
      (node (ref "R46") (pin "2") (pinfunction "2_2") (pintype "passive"))
    )
    (net (code "22") (name "Net-(IC5B--IN)") (class "Default")
      (node (ref "IC5") (pin "6") (pinfunction "-IN_6") (pintype "input"))
      (node (ref "R46") (pin "1") (pinfunction "1_1") (pintype "passive"))
      (node (ref "R47") (pin "2") (pinfunction "2_2") (pintype "passive"))
    )
    (net (code "23") (name "Net-(IC5B-OUT)") (class "Default")
      (node (ref "C34") (pin "+") (pinfunction "+_+") (pintype "passive"))
      (node (ref "IC5") (pin "7") (pinfunction "OUT_7") (pintype "output"))
      (node (ref "R47") (pin "1") (pinfunction "1_1") (pintype "passive"))
    )
    (net (code "24") (name "Net-(IC6A--IN)") (class "Default")
      (node (ref "C29") (pin "1") (pinfunction "1_1") (pintype "passive"))
      (node (ref "IC6") (pin "2") (pinfunction "-IN_2") (pintype "input"))
      (node (ref "R11") (pin "1") (pinfunction "1_1") (pintype "passive"))
      (node (ref "R18") (pin "1") (pinfunction "1_1") (pintype "passive"))
      (node (ref "R23") (pin "1") (pinfunction "1_1") (pintype "passive"))
      (node (ref "R30") (pin "1") (pinfunction "1_1") (pintype "passive"))
      (node (ref "R36") (pin "1") (pinfunction "1_1") (pintype "passive"))
      (node (ref "R41") (pin "1") (pinfunction "1_1") (pintype "passive"))
      (node (ref "R48") (pin "2") (pinfunction "2_2") (pintype "passive"))
    )
    (net (code "25") (name "Net-(IC6A-OUT)") (class "Default")
      (node (ref "C29") (pin "2") (pinfunction "2_2") (pintype "passive"))
      (node (ref "IC6") (pin "1") (pinfunction "OUT_1") (pintype "output"))
      (node (ref "R48") (pin "1") (pinfunction "1_1") (pintype "passive"))
      (node (ref "R49") (pin "2") (pinfunction "2_2") (pintype "passive"))
    )
    (net (code "26") (name "Net-(IC6B--IN)") (class "Default")
      (node (ref "IC6") (pin "6") (pinfunction "-IN_6") (pintype "input"))
      (node (ref "R49") (pin "1") (pinfunction "1_1") (pintype "passive"))
      (node (ref "R51") (pin "2") (pinfunction "2_2") (pintype "passive"))
    )
    (net (code "27") (name "Net-(IC6B-OUT)") (class "Default")
      (node (ref "C35") (pin "+") (pinfunction "+_+") (pintype "passive"))
      (node (ref "IC6") (pin "7") (pinfunction "OUT_7") (pintype "output"))
      (node (ref "R51") (pin "1") (pinfunction "1_1") (pintype "passive"))
    )
    (net (code "28") (name "Net-(IC7A--IN)") (class "Default")
      (node (ref "C30") (pin "1") (pinfunction "1_1") (pintype "passive"))
      (node (ref "IC7") (pin "2") (pinfunction "-IN_2") (pintype "input"))
      (node (ref "R12") (pin "1") (pinfunction "1_1") (pintype "passive"))
      (node (ref "R17") (pin "1") (pinfunction "1_1") (pintype "passive"))
      (node (ref "R24") (pin "1") (pinfunction "1_1") (pintype "passive"))
      (node (ref "R29") (pin "1") (pinfunction "1_1") (pintype "passive"))
      (node (ref "R35") (pin "1") (pinfunction "1_1") (pintype "passive"))
      (node (ref "R42") (pin "1") (pinfunction "1_1") (pintype "passive"))
      (node (ref "R52") (pin "2") (pinfunction "2_2") (pintype "passive"))
    )
    (net (code "29") (name "Net-(IC7A-OUT)") (class "Default")
      (node (ref "C30") (pin "2") (pinfunction "2_2") (pintype "passive"))
      (node (ref "IC7") (pin "1") (pinfunction "OUT_1") (pintype "output"))
      (node (ref "R52") (pin "1") (pinfunction "1_1") (pintype "passive"))
      (node (ref "R53") (pin "2") (pinfunction "2_2") (pintype "passive"))
    )
    (net (code "30") (name "Net-(IC7B--IN)") (class "Default")
      (node (ref "IC7") (pin "6") (pinfunction "-IN_6") (pintype "input"))
      (node (ref "R53") (pin "1") (pinfunction "1_1") (pintype "passive"))
      (node (ref "R54") (pin "2") (pinfunction "2_2") (pintype "passive"))
    )
    (net (code "31") (name "Net-(IC7B-OUT)") (class "Default")
      (node (ref "C36") (pin "+") (pinfunction "+_+") (pintype "passive"))
      (node (ref "IC7") (pin "7") (pinfunction "OUT_7") (pintype "output"))
      (node (ref "R54") (pin "1") (pinfunction "1_1") (pintype "passive"))
    )
    (net (code "32") (name "Net-(IC8A--IN)") (class "Default")
      (node (ref "C31") (pin "1") (pinfunction "1_1") (pintype "passive"))
      (node (ref "IC8") (pin "2") (pinfunction "-IN_2") (pintype "input"))
      (node (ref "R13") (pin "1") (pinfunction "1_1") (pintype "passive"))
      (node (ref "R16") (pin "1") (pinfunction "1_1") (pintype "passive"))
      (node (ref "R25") (pin "1") (pinfunction "1_1") (pintype "passive"))
      (node (ref "R28") (pin "1") (pinfunction "1_1") (pintype "passive"))
      (node (ref "R34") (pin "1") (pinfunction "1_1") (pintype "passive"))
      (node (ref "R43") (pin "1") (pinfunction "1_1") (pintype "passive"))
      (node (ref "R55") (pin "2") (pinfunction "2_2") (pintype "passive"))
    )
    (net (code "33") (name "Net-(IC8A-OUT)") (class "Default")
      (node (ref "C31") (pin "2") (pinfunction "2_2") (pintype "passive"))
      (node (ref "IC8") (pin "1") (pinfunction "OUT_1") (pintype "output"))
      (node (ref "R55") (pin "1") (pinfunction "1_1") (pintype "passive"))
      (node (ref "R56") (pin "2") (pinfunction "2_2") (pintype "passive"))
    )
    (net (code "34") (name "Net-(IC8B--IN)") (class "Default")
      (node (ref "IC8") (pin "6") (pinfunction "-IN_6") (pintype "input"))
      (node (ref "R56") (pin "1") (pinfunction "1_1") (pintype "passive"))
      (node (ref "R57") (pin "2") (pinfunction "2_2") (pintype "passive"))
    )
    (net (code "35") (name "Net-(IC8B-OUT)") (class "Default")
      (node (ref "C37") (pin "+") (pinfunction "+_+") (pintype "passive"))
      (node (ref "IC8") (pin "7") (pinfunction "OUT_7") (pintype "output"))
      (node (ref "R57") (pin "1") (pinfunction "1_1") (pintype "passive"))
    )
    (net (code "36") (name "Net-(IC9A--IN)") (class "Default")
      (node (ref "C32") (pin "1") (pinfunction "1_1") (pintype "passive"))
      (node (ref "IC9") (pin "2") (pinfunction "-IN_2") (pintype "input"))
      (node (ref "R14") (pin "1") (pinfunction "1_1") (pintype "passive"))
      (node (ref "R15") (pin "1") (pinfunction "1_1") (pintype "passive"))
      (node (ref "R26") (pin "1") (pinfunction "1_1") (pintype "passive"))
      (node (ref "R27") (pin "1") (pinfunction "1_1") (pintype "passive"))
      (node (ref "R33") (pin "1") (pinfunction "1_1") (pintype "passive"))
      (node (ref "R44") (pin "1") (pinfunction "1_1") (pintype "passive"))
      (node (ref "R58") (pin "2") (pinfunction "2_2") (pintype "passive"))
    )
    (net (code "37") (name "Net-(IC9A-OUT)") (class "Default")
      (node (ref "C32") (pin "2") (pinfunction "2_2") (pintype "passive"))
      (node (ref "IC9") (pin "1") (pinfunction "OUT_1") (pintype "output"))
      (node (ref "R58") (pin "1") (pinfunction "1_1") (pintype "passive"))
      (node (ref "R59") (pin "2") (pinfunction "2_2") (pintype "passive"))
    )
    (net (code "38") (name "Net-(IC9B--IN)") (class "Default")
      (node (ref "IC9") (pin "6") (pinfunction "-IN_6") (pintype "input"))
      (node (ref "R59") (pin "1") (pinfunction "1_1") (pintype "passive"))
      (node (ref "R60") (pin "2") (pinfunction "2_2") (pintype "passive"))
    )
    (net (code "39") (name "Net-(IC9B-OUT)") (class "Default")
      (node (ref "C38") (pin "+") (pinfunction "+_+") (pintype "passive"))
      (node (ref "IC9") (pin "7") (pinfunction "OUT_7") (pintype "output"))
      (node (ref "R60") (pin "1") (pinfunction "1_1") (pintype "passive"))
    )
    (net (code "40") (name "Net-(L1-C)") (class "Default")
      (node (ref "L1") (pin "K") (pinfunction "C_K") (pintype "passive"))
      (node (ref "Q1") (pin "C") (pinfunction "C_C") (pintype "passive"))
    )
    (net (code "41") (name "Net-(L2-C)") (class "Default")
      (node (ref "L2") (pin "K") (pinfunction "C_K") (pintype "passive"))
      (node (ref "Q2") (pin "C") (pinfunction "C_C") (pintype "passive"))
    )
    (net (code "42") (name "Net-(L3-C)") (class "Default")
      (node (ref "L3") (pin "K") (pinfunction "C_K") (pintype "passive"))
      (node (ref "Q3") (pin "C") (pinfunction "C_C") (pintype "passive"))
    )
    (net (code "43") (name "Net-(L4-C)") (class "Default")
      (node (ref "L4") (pin "K") (pinfunction "C_K") (pintype "passive"))
      (node (ref "Q4") (pin "C") (pinfunction "C_C") (pintype "passive"))
    )
    (net (code "44") (name "Net-(L5-C)") (class "Default")
      (node (ref "L5") (pin "K") (pinfunction "C_K") (pintype "passive"))
      (node (ref "Q5") (pin "C") (pinfunction "C_C") (pintype "passive"))
    )
    (net (code "45") (name "Net-(L6-C)") (class "Default")
      (node (ref "L6") (pin "K") (pinfunction "C_K") (pintype "passive"))
      (node (ref "Q6") (pin "C") (pinfunction "C_C") (pintype "passive"))
    )
    (net (code "46") (name "Net-(Q1-PadE)") (class "Default")
      (node (ref "Q1") (pin "E") (pinfunction "E_E") (pintype "passive"))
      (node (ref "R1") (pin "1") (pinfunction "1_1") (pintype "passive"))
    )
    (net (code "47") (name "Net-(Q2-PadE)") (class "Default")
      (node (ref "Q2") (pin "E") (pinfunction "E_E") (pintype "passive"))
      (node (ref "R2") (pin "1") (pinfunction "1_1") (pintype "passive"))
    )
    (net (code "48") (name "Net-(Q3-PadE)") (class "Default")
      (node (ref "Q3") (pin "E") (pinfunction "E_E") (pintype "passive"))
      (node (ref "R3") (pin "1") (pinfunction "1_1") (pintype "passive"))
    )
    (net (code "49") (name "Net-(Q4-PadE)") (class "Default")
      (node (ref "Q4") (pin "E") (pinfunction "E_E") (pintype "passive"))
      (node (ref "R4") (pin "1") (pinfunction "1_1") (pintype "passive"))
    )
    (net (code "50") (name "Net-(Q5-PadE)") (class "Default")
      (node (ref "Q5") (pin "E") (pinfunction "E_E") (pintype "passive"))
      (node (ref "R5") (pin "1") (pinfunction "1_1") (pintype "passive"))
    )
    (net (code "51") (name "Net-(Q6-PadE)") (class "Default")
      (node (ref "Q6") (pin "E") (pinfunction "E_E") (pintype "passive"))
      (node (ref "R6") (pin "1") (pinfunction "1_1") (pintype "passive"))
    )
    (net (code "52") (name "Net-(VR1-E)") (class "Default")
      (node (ref "C15") (pin "-") (pinfunction "-_-") (pintype "passive"))
      (node (ref "VR1") (pin "P$1") (pinfunction "E_P$1") (pintype "passive"))
      (node (ref "VR2") (pin "P$1") (pinfunction "E_P$1") (pintype "passive"))
      (node (ref "VR3") (pin "P$1") (pinfunction "E_P$1") (pintype "passive"))
      (node (ref "VR4") (pin "P$1") (pinfunction "E_P$1") (pintype "passive"))
      (node (ref "VR5") (pin "P$1") (pinfunction "E_P$1") (pintype "passive"))
      (node (ref "VR6") (pin "P$1") (pinfunction "E_P$1") (pintype "passive"))
    )
    (net (code "53") (name "Net-(VR1-S)") (class "Default")
      (node (ref "R9") (pin "2") (pinfunction "2_2") (pintype "passive"))
      (node (ref "VR1") (pin "P$2") (pinfunction "S_P$2") (pintype "passive"))
    )
    (net (code "54") (name "Net-(VR2-S)") (class "Default")
      (node (ref "R10") (pin "2") (pinfunction "2_2") (pintype "passive"))
      (node (ref "VR2") (pin "P$2") (pinfunction "S_P$2") (pintype "passive"))
    )
    (net (code "55") (name "Net-(VR3-S)") (class "Default")
      (node (ref "R11") (pin "2") (pinfunction "2_2") (pintype "passive"))
      (node (ref "VR3") (pin "P$2") (pinfunction "S_P$2") (pintype "passive"))
    )
    (net (code "56") (name "Net-(VR4-S)") (class "Default")
      (node (ref "R12") (pin "2") (pinfunction "2_2") (pintype "passive"))
      (node (ref "VR4") (pin "P$2") (pinfunction "S_P$2") (pintype "passive"))
    )
    (net (code "57") (name "Net-(VR5-S)") (class "Default")
      (node (ref "R13") (pin "2") (pinfunction "2_2") (pintype "passive"))
      (node (ref "VR5") (pin "P$2") (pinfunction "S_P$2") (pintype "passive"))
    )
    (net (code "58") (name "Net-(VR6-S)") (class "Default")
      (node (ref "R14") (pin "2") (pinfunction "2_2") (pintype "passive"))
      (node (ref "VR6") (pin "P$2") (pinfunction "S_P$2") (pintype "passive"))
    )
    (net (code "59") (name "Net-(VR7-S)") (class "Default")
      (node (ref "R20") (pin "2") (pinfunction "2_2") (pintype "passive"))
      (node (ref "VR7") (pin "P$2") (pinfunction "S_P$2") (pintype "passive"))
    )
    (net (code "60") (name "Net-(VR8-S)") (class "Default")
      (node (ref "R19") (pin "2") (pinfunction "2_2") (pintype "passive"))
      (node (ref "VR8") (pin "P$2") (pinfunction "S_P$2") (pintype "passive"))
    )
    (net (code "61") (name "Net-(VR9-S)") (class "Default")
      (node (ref "R18") (pin "2") (pinfunction "2_2") (pintype "passive"))
      (node (ref "VR9") (pin "P$2") (pinfunction "S_P$2") (pintype "passive"))
    )
    (net (code "62") (name "Net-(VR10-E)") (class "Default")
      (node (ref "C16") (pin "-") (pinfunction "-_-") (pintype "passive"))
      (node (ref "VR10") (pin "P$1") (pinfunction "E_P$1") (pintype "passive"))
      (node (ref "VR11") (pin "P$1") (pinfunction "E_P$1") (pintype "passive"))
      (node (ref "VR12") (pin "P$1") (pinfunction "E_P$1") (pintype "passive"))
      (node (ref "VR7") (pin "P$1") (pinfunction "E_P$1") (pintype "passive"))
      (node (ref "VR8") (pin "P$1") (pinfunction "E_P$1") (pintype "passive"))
      (node (ref "VR9") (pin "P$1") (pinfunction "E_P$1") (pintype "passive"))
    )
    (net (code "63") (name "Net-(VR10-S)") (class "Default")
      (node (ref "R17") (pin "2") (pinfunction "2_2") (pintype "passive"))
      (node (ref "VR10") (pin "P$2") (pinfunction "S_P$2") (pintype "passive"))
    )
    (net (code "64") (name "Net-(VR11-S)") (class "Default")
      (node (ref "R16") (pin "2") (pinfunction "2_2") (pintype "passive"))
      (node (ref "VR11") (pin "P$2") (pinfunction "S_P$2") (pintype "passive"))
    )
    (net (code "65") (name "Net-(VR12-S)") (class "Default")
      (node (ref "R15") (pin "2") (pinfunction "2_2") (pintype "passive"))
      (node (ref "VR12") (pin "P$2") (pinfunction "S_P$2") (pintype "passive"))
    )
    (net (code "66") (name "Net-(VR13-E)") (class "Default")
      (node (ref "C17") (pin "-") (pinfunction "-_-") (pintype "passive"))
      (node (ref "VR13") (pin "P$1") (pinfunction "E_P$1") (pintype "passive"))
      (node (ref "VR14") (pin "P$1") (pinfunction "E_P$1") (pintype "passive"))
      (node (ref "VR15") (pin "P$1") (pinfunction "E_P$1") (pintype "passive"))
      (node (ref "VR16") (pin "P$1") (pinfunction "E_P$1") (pintype "passive"))
      (node (ref "VR17") (pin "P$1") (pinfunction "E_P$1") (pintype "passive"))
      (node (ref "VR18") (pin "P$1") (pinfunction "E_P$1") (pintype "passive"))
    )
    (net (code "67") (name "Net-(VR13-S)") (class "Default")
      (node (ref "R21") (pin "2") (pinfunction "2_2") (pintype "passive"))
      (node (ref "VR13") (pin "P$2") (pinfunction "S_P$2") (pintype "passive"))
    )
    (net (code "68") (name "Net-(VR14-S)") (class "Default")
      (node (ref "R22") (pin "2") (pinfunction "2_2") (pintype "passive"))
      (node (ref "VR14") (pin "P$2") (pinfunction "S_P$2") (pintype "passive"))
    )
    (net (code "69") (name "Net-(VR15-S)") (class "Default")
      (node (ref "R23") (pin "2") (pinfunction "2_2") (pintype "passive"))
      (node (ref "VR15") (pin "P$2") (pinfunction "S_P$2") (pintype "passive"))
    )
    (net (code "70") (name "Net-(VR16-S)") (class "Default")
      (node (ref "R24") (pin "2") (pinfunction "2_2") (pintype "passive"))
      (node (ref "VR16") (pin "P$2") (pinfunction "S_P$2") (pintype "passive"))
    )
    (net (code "71") (name "Net-(VR17-S)") (class "Default")
      (node (ref "R25") (pin "2") (pinfunction "2_2") (pintype "passive"))
      (node (ref "VR17") (pin "P$2") (pinfunction "S_P$2") (pintype "passive"))
    )
    (net (code "72") (name "Net-(VR18-S)") (class "Default")
      (node (ref "R26") (pin "2") (pinfunction "2_2") (pintype "passive"))
      (node (ref "VR18") (pin "P$2") (pinfunction "S_P$2") (pintype "passive"))
    )
    (net (code "73") (name "Net-(VR19-E)") (class "Default")
      (node (ref "C18") (pin "-") (pinfunction "-_-") (pintype "passive"))
      (node (ref "VR19") (pin "P$1") (pinfunction "E_P$1") (pintype "passive"))
      (node (ref "VR20") (pin "P$1") (pinfunction "E_P$1") (pintype "passive"))
      (node (ref "VR21") (pin "P$1") (pinfunction "E_P$1") (pintype "passive"))
      (node (ref "VR22") (pin "P$1") (pinfunction "E_P$1") (pintype "passive"))
      (node (ref "VR23") (pin "P$1") (pinfunction "E_P$1") (pintype "passive"))
      (node (ref "VR24") (pin "P$1") (pinfunction "E_P$1") (pintype "passive"))
    )
    (net (code "74") (name "Net-(VR19-S)") (class "Default")
      (node (ref "R32") (pin "2") (pinfunction "2_2") (pintype "passive"))
      (node (ref "VR19") (pin "P$2") (pinfunction "S_P$2") (pintype "passive"))
    )
    (net (code "75") (name "Net-(VR20-S)") (class "Default")
      (node (ref "R31") (pin "2") (pinfunction "2_2") (pintype "passive"))
      (node (ref "VR20") (pin "P$2") (pinfunction "S_P$2") (pintype "passive"))
    )
    (net (code "76") (name "Net-(VR21-S)") (class "Default")
      (node (ref "R30") (pin "2") (pinfunction "2_2") (pintype "passive"))
      (node (ref "VR21") (pin "P$2") (pinfunction "S_P$2") (pintype "passive"))
    )
    (net (code "77") (name "Net-(VR22-S)") (class "Default")
      (node (ref "R29") (pin "2") (pinfunction "2_2") (pintype "passive"))
      (node (ref "VR22") (pin "P$2") (pinfunction "S_P$2") (pintype "passive"))
    )
    (net (code "78") (name "Net-(VR23-S)") (class "Default")
      (node (ref "R28") (pin "2") (pinfunction "2_2") (pintype "passive"))
      (node (ref "VR23") (pin "P$2") (pinfunction "S_P$2") (pintype "passive"))
    )
    (net (code "79") (name "Net-(VR24-S)") (class "Default")
      (node (ref "R27") (pin "2") (pinfunction "2_2") (pintype "passive"))
      (node (ref "VR24") (pin "P$2") (pinfunction "S_P$2") (pintype "passive"))
    )
    (net (code "80") (name "Net-(VR25-E)") (class "Default")
      (node (ref "C19") (pin "-") (pinfunction "-_-") (pintype "passive"))
      (node (ref "VR25") (pin "P$1") (pinfunction "E_P$1") (pintype "passive"))
      (node (ref "VR26") (pin "P$1") (pinfunction "E_P$1") (pintype "passive"))
      (node (ref "VR27") (pin "P$1") (pinfunction "E_P$1") (pintype "passive"))
      (node (ref "VR28") (pin "P$1") (pinfunction "E_P$1") (pintype "passive"))
      (node (ref "VR29") (pin "P$1") (pinfunction "E_P$1") (pintype "passive"))
      (node (ref "VR30") (pin "P$1") (pinfunction "E_P$1") (pintype "passive"))
    )
    (net (code "81") (name "Net-(VR25-S)") (class "Default")
      (node (ref "R38") (pin "2") (pinfunction "2_2") (pintype "passive"))
      (node (ref "VR25") (pin "P$2") (pinfunction "S_P$2") (pintype "passive"))
    )
    (net (code "82") (name "Net-(VR26-S)") (class "Default")
      (node (ref "R37") (pin "2") (pinfunction "2_2") (pintype "passive"))
      (node (ref "VR26") (pin "P$2") (pinfunction "S_P$2") (pintype "passive"))
    )
    (net (code "83") (name "Net-(VR27-S)") (class "Default")
      (node (ref "R36") (pin "2") (pinfunction "2_2") (pintype "passive"))
      (node (ref "VR27") (pin "P$2") (pinfunction "S_P$2") (pintype "passive"))
    )
    (net (code "84") (name "Net-(VR28-S)") (class "Default")
      (node (ref "R35") (pin "2") (pinfunction "2_2") (pintype "passive"))
      (node (ref "VR28") (pin "P$2") (pinfunction "S_P$2") (pintype "passive"))
    )
    (net (code "85") (name "Net-(VR29-S)") (class "Default")
      (node (ref "R34") (pin "2") (pinfunction "2_2") (pintype "passive"))
      (node (ref "VR29") (pin "P$2") (pinfunction "S_P$2") (pintype "passive"))
    )
    (net (code "86") (name "Net-(VR30-S)") (class "Default")
      (node (ref "R33") (pin "2") (pinfunction "2_2") (pintype "passive"))
      (node (ref "VR30") (pin "P$2") (pinfunction "S_P$2") (pintype "passive"))
    )
    (net (code "87") (name "Net-(VR31-E)") (class "Default")
      (node (ref "C20") (pin "-") (pinfunction "-_-") (pintype "passive"))
      (node (ref "VR31") (pin "P$1") (pinfunction "E_P$1") (pintype "passive"))
      (node (ref "VR32") (pin "P$1") (pinfunction "E_P$1") (pintype "passive"))
      (node (ref "VR33") (pin "P$1") (pinfunction "E_P$1") (pintype "passive"))
      (node (ref "VR34") (pin "P$1") (pinfunction "E_P$1") (pintype "passive"))
      (node (ref "VR35") (pin "P$1") (pinfunction "E_P$1") (pintype "passive"))
      (node (ref "VR36") (pin "P$1") (pinfunction "E_P$1") (pintype "passive"))
    )
    (net (code "88") (name "Net-(VR31-S)") (class "Default")
      (node (ref "R39") (pin "2") (pinfunction "2_2") (pintype "passive"))
      (node (ref "VR31") (pin "P$2") (pinfunction "S_P$2") (pintype "passive"))
    )
    (net (code "89") (name "Net-(VR32-S)") (class "Default")
      (node (ref "R40") (pin "2") (pinfunction "2_2") (pintype "passive"))
      (node (ref "VR32") (pin "P$2") (pinfunction "S_P$2") (pintype "passive"))
    )
    (net (code "90") (name "Net-(VR33-S)") (class "Default")
      (node (ref "R41") (pin "2") (pinfunction "2_2") (pintype "passive"))
      (node (ref "VR33") (pin "P$2") (pinfunction "S_P$2") (pintype "passive"))
    )
    (net (code "91") (name "Net-(VR34-S)") (class "Default")
      (node (ref "R42") (pin "2") (pinfunction "2_2") (pintype "passive"))
      (node (ref "VR34") (pin "P$2") (pinfunction "S_P$2") (pintype "passive"))
    )
    (net (code "92") (name "Net-(VR35-S)") (class "Default")
      (node (ref "R43") (pin "2") (pinfunction "2_2") (pintype "passive"))
      (node (ref "VR35") (pin "P$2") (pinfunction "S_P$2") (pintype "passive"))
    )
    (net (code "93") (name "Net-(VR36-S)") (class "Default")
      (node (ref "R44") (pin "2") (pinfunction "2_2") (pintype "passive"))
      (node (ref "VR36") (pin "P$2") (pinfunction "S_P$2") (pintype "passive"))
    )
    (net (code "94") (name "VCC") (class "Default")
      (node (ref "C1") (pin "+") (pinfunction "+_+") (pintype "passive"))
      (node (ref "C11") (pin "1") (pinfunction "1_1") (pintype "passive"))
      (node (ref "C13") (pin "1") (pinfunction "1_1") (pintype "passive"))
      (node (ref "C21") (pin "1") (pinfunction "1_1") (pintype "passive"))
      (node (ref "C22") (pin "1") (pinfunction "1_1") (pintype "passive"))
      (node (ref "C23") (pin "1") (pinfunction "1_1") (pintype "passive"))
      (node (ref "C9") (pin "1") (pinfunction "1_1") (pintype "passive"))
      (node (ref "D1") (pin "C") (pinfunction "C_C") (pintype "passive"))
      (node (ref "IC4") (pin "8") (pinfunction "V+_8") (pintype "power_in"))
      (node (ref "IC5") (pin "8") (pinfunction "V+_8") (pintype "power_in"))
      (node (ref "IC6") (pin "8") (pinfunction "V+_8") (pintype "power_in"))
      (node (ref "IC7") (pin "8") (pinfunction "V+_8") (pintype "power_in"))
      (node (ref "IC8") (pin "8") (pinfunction "V+_8") (pintype "power_in"))
      (node (ref "IC9") (pin "8") (pinfunction "V+_8") (pintype "power_in"))
      (node (ref "L1") (pin "A") (pinfunction "A_A") (pintype "passive"))
      (node (ref "L2") (pin "A") (pinfunction "A_A") (pintype "passive"))
      (node (ref "L3") (pin "A") (pinfunction "A_A") (pintype "passive"))
      (node (ref "L4") (pin "A") (pinfunction "A_A") (pintype "passive"))
      (node (ref "L5") (pin "A") (pinfunction "A_A") (pintype "passive"))
      (node (ref "L6") (pin "A") (pinfunction "A_A") (pintype "passive"))
    )
    (net (code "95") (name "VEE") (class "Default")
      (node (ref "C10") (pin "2") (pinfunction "2_2") (pintype "passive"))
      (node (ref "C12") (pin "2") (pinfunction "2_2") (pintype "passive"))
      (node (ref "C14") (pin "2") (pinfunction "2_2") (pintype "passive"))
      (node (ref "C2") (pin "-") (pinfunction "-_-") (pintype "passive"))
      (node (ref "C24") (pin "2") (pinfunction "2_2") (pintype "passive"))
      (node (ref "C25") (pin "2") (pinfunction "2_2") (pintype "passive"))
      (node (ref "C26") (pin "2") (pinfunction "2_2") (pintype "passive"))
      (node (ref "D2") (pin "A") (pinfunction "A_A") (pintype "passive"))
      (node (ref "IC4") (pin "4") (pinfunction "V-_4") (pintype "power_in"))
      (node (ref "IC5") (pin "4") (pinfunction "V-_4") (pintype "power_in"))
      (node (ref "IC6") (pin "4") (pinfunction "V-_4") (pintype "power_in"))
      (node (ref "IC7") (pin "4") (pinfunction "V-_4") (pintype "power_in"))
      (node (ref "IC8") (pin "4") (pinfunction "V-_4") (pintype "power_in"))
      (node (ref "IC9") (pin "4") (pinfunction "V-_4") (pintype "power_in"))
    )
    (net (code "96") (name "unconnected-(1-2-PadP2)") (class "Default")
      (node (ref "1") (pin "P2") (pinfunction "2_P2") (pintype "passive"))
    )
    (net (code "97") (name "unconnected-(2-2-PadP2)") (class "Default")
      (node (ref "2") (pin "P2") (pinfunction "2_P2") (pintype "passive"))
    )
    (net (code "98") (name "unconnected-(3-2-PadP2)") (class "Default")
      (node (ref "3") (pin "P2") (pinfunction "2_P2") (pintype "passive"))
    )
    (net (code "99") (name "unconnected-(4-2-PadP2)") (class "Default")
      (node (ref "4") (pin "P2") (pinfunction "2_P2") (pintype "passive"))
    )
    (net (code "100") (name "unconnected-(5-2-PadP2)") (class "Default")
      (node (ref "5") (pin "P2") (pinfunction "2_P2") (pintype "passive"))
    )
    (net (code "101") (name "unconnected-(6-2-PadP2)") (class "Default")
      (node (ref "6") (pin "P2") (pinfunction "2_P2") (pintype "passive"))
    )
    (net (code "102") (name "unconnected-(7-2-PadP2)") (class "Default")
      (node (ref "7") (pin "P2") (pinfunction "2_P2") (pintype "passive"))
    )
    (net (code "103") (name "unconnected-(8-2-PadP2)") (class "Default")
      (node (ref "8") (pin "P2") (pinfunction "2_P2") (pintype "passive"))
    )
    (net (code "104") (name "unconnected-(9-2-PadP2)") (class "Default")
      (node (ref "9") (pin "P2") (pinfunction "2_P2") (pintype "passive"))
    )
    (net (code "105") (name "unconnected-(10-2-PadP2)") (class "Default")
      (node (ref "10") (pin "P2") (pinfunction "2_P2") (pintype "passive"))
    )
    (net (code "106") (name "unconnected-(11-2-PadP2)") (class "Default")
      (node (ref "11") (pin "P2") (pinfunction "2_P2") (pintype "passive"))
    )
    (net (code "107") (name "unconnected-(12-2-PadP2)") (class "Default")
      (node (ref "12") (pin "P2") (pinfunction "2_P2") (pintype "passive"))
    )
  )
)
